# Buttons.net
KiCad netlist of a schematic drawn in Altium Designer
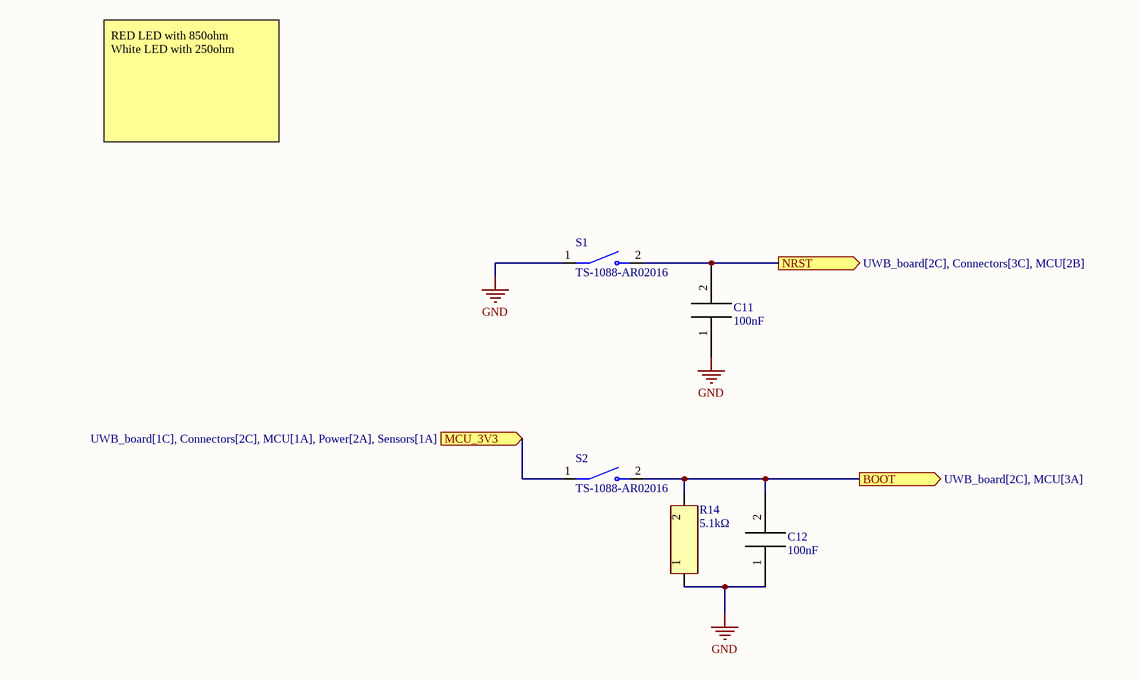
[diagram p0: Buttons.SchDoc]

(export (version "E")
  (design (tool "Eeschema 10.0.6"))
  (components
    (comp (ref "C11")
      (value "100nF")
      (footprint "0603_cap")
      (description "100nF 50V X7R ±10% 0603 Multilayer Ceramic Capacitors MLCC - SMD/SMT ROHS")
      (fields (field (name "LCSC PART #") "C14663"))
      (libsource (lib "Schlib1") (part "CC0603KRX7R9BB104"))
    )
    (comp (ref "C12")
      (value "100nF")
      (footprint "0603_cap")
      (description "100nF 50V X7R ±10% 0603 Multilayer Ceramic Capacitors MLCC - SMD/SMT ROHS")
      (fields (field (name "LCSC PART #") "C14663"))
      (libsource (lib "Schlib1") (part "CC0603KRX7R9BB104"))
    )
    (comp (ref "R14")
      (value "5.1kΩ")
      (footprint "0603_res")
      (fields (field (name "LCSC PART #") "C23186") (field (name "Comment") "5.1k"))
      (libsource (lib "Schlib1") (part "0603WAF5101T5E"))
    )
    (comp (ref "S1")
      (value "TS-1088-AR02016")
      (footprint "SW_TS-1088-AR02016")
      (fields (field (name "LCSC PART #") "C720477"))
      (libsource (lib "Schlib1") (part "TS-1088-AR02016"))
    )
    (comp (ref "S2")
      (value "TS-1088-AR02016")
      (footprint "SW_TS-1088-AR02016")
      (fields (field (name "LCSC PART #") "C720477"))
      (libsource (lib "Schlib1") (part "TS-1088-AR02016"))
    )
  )
  (nets
    (net (code "1") (name "/BOOT") (class "Default")
      (node (ref "C12") (pin "2") (pinfunction "3_2") (pintype "passive"))
      (node (ref "R14") (pin "2") (pinfunction "3_2") (pintype "passive"))
      (node (ref "S2") (pin "2") (pinfunction "2_2") (pintype "passive"))
    )
    (net (code "2") (name "/MCU_3V3") (class "Default")
      (node (ref "S2") (pin "1") (pinfunction "1_1") (pintype "passive"))
    )
    (net (code "3") (name "/NRST") (class "Default")
      (node (ref "C11") (pin "2") (pinfunction "3_2") (pintype "passive"))
      (node (ref "S1") (pin "2") (pinfunction "2_2") (pintype "passive"))
    )
    (net (code "4") (name "GND") (class "Default")
      (node (ref "C11") (pin "1") (pintype "passive"))
      (node (ref "C12") (pin "1") (pintype "passive"))
      (node (ref "R14") (pin "1") (pinfunction "1_1") (pintype "passive"))
      (node (ref "S1") (pin "1") (pinfunction "1_1") (pintype "passive"))
    )
  )
)
